# SPI_Output.net
KiCad netlist of a schematic drawn in Altium Designer
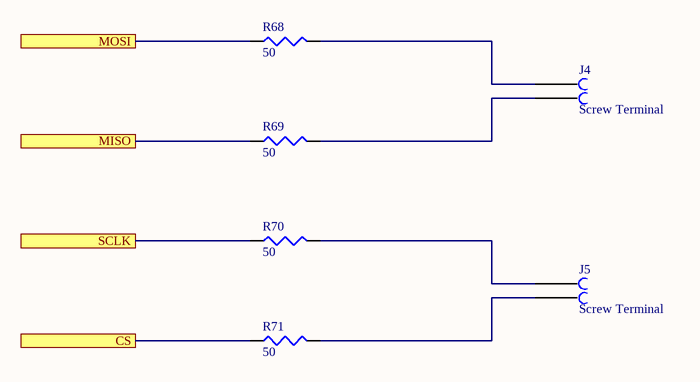
[diagram p0: SPI Output.SchDoc]

(export (version "E")
  (design (tool "Eeschema 10.0.6"))
  (components
    (comp (ref "J4")
      (value "Screw Terminal")
      (footprint "Screw Terminal")
      (libsource (lib "AvionicsParts") (part "Screw Terminal"))
    )
    (comp (ref "J5")
      (value "Screw Terminal")
      (footprint "Screw Terminal")
      (libsource (lib "AvionicsParts") (part "Screw Terminal"))
    )
    (comp (ref "R68")
      (value "50")
      (footprint "0603 Footprint")
      (description "Resistor")
      (fields (field (name "Comment") "Res3") (field (name "PUBLISHER") "Altium Limited"))
      (libsource (lib "Miscellaneous Devices") (part "Res3"))
    )
    (comp (ref "R69")
      (value "50")
      (footprint "0603 Footprint")
      (description "Resistor")
      (fields (field (name "Comment") "Res3") (field (name "PUBLISHER") "Altium Limited"))
      (libsource (lib "Miscellaneous Devices") (part "Res3"))
    )
    (comp (ref "R70")
      (value "50")
      (footprint "0603 Footprint")
      (description "Resistor")
      (fields (field (name "Comment") "Res3") (field (name "PUBLISHER") "Altium Limited"))
      (libsource (lib "Miscellaneous Devices") (part "Res3"))
    )
    (comp (ref "R71")
      (value "50")
      (footprint "0603 Footprint")
      (description "Resistor")
      (fields (field (name "Comment") "Res3") (field (name "PUBLISHER") "Altium Limited"))
      (libsource (lib "Miscellaneous Devices") (part "Res3"))
    )
  )
  (nets
    (net (code "1") (name "/CS") (class "Default")
      (node (ref "R71") (pin "1") (pinfunction "1_1") (pintype "passive"))
    )
    (net (code "2") (name "/MISO") (class "Default")
      (node (ref "R69") (pin "1") (pinfunction "1_1") (pintype "passive"))
    )
    (net (code "3") (name "/MOSI") (class "Default")
      (node (ref "R68") (pin "1") (pinfunction "1_1") (pintype "passive"))
    )
    (net (code "4") (name "/SCLK") (class "Default")
      (node (ref "R70") (pin "1") (pinfunction "1_1") (pintype "passive"))
    )
    (net (code "5") (name "Net-(J4-Pad1)") (class "Default")
      (node (ref "J4") (pin "1") (pinfunction "1_1") (pintype "passive"))
      (node (ref "R68") (pin "2") (pinfunction "2_2") (pintype "passive"))
    )
    (net (code "6") (name "Net-(J4-Pad2)") (class "Default")
      (node (ref "J4") (pin "2") (pinfunction "2_2") (pintype "passive"))
      (node (ref "R69") (pin "2") (pinfunction "2_2") (pintype "passive"))
    )
    (net (code "7") (name "Net-(J5-Pad1)") (class "Default")
      (node (ref "J5") (pin "1") (pinfunction "1_1") (pintype "passive"))
      (node (ref "R70") (pin "2") (pinfunction "2_2") (pintype "passive"))
    )
    (net (code "8") (name "Net-(J5-Pad2)") (class "Default")
      (node (ref "J5") (pin "2") (pinfunction "2_2") (pintype "passive"))
      (node (ref "R71") (pin "2") (pinfunction "2_2") (pintype "passive"))
    )
  )
)
